# NMEA_BatteryMonitor_ESP32_D1_Mini.net
KiCad netlist of a schematic drawn in EAGLE
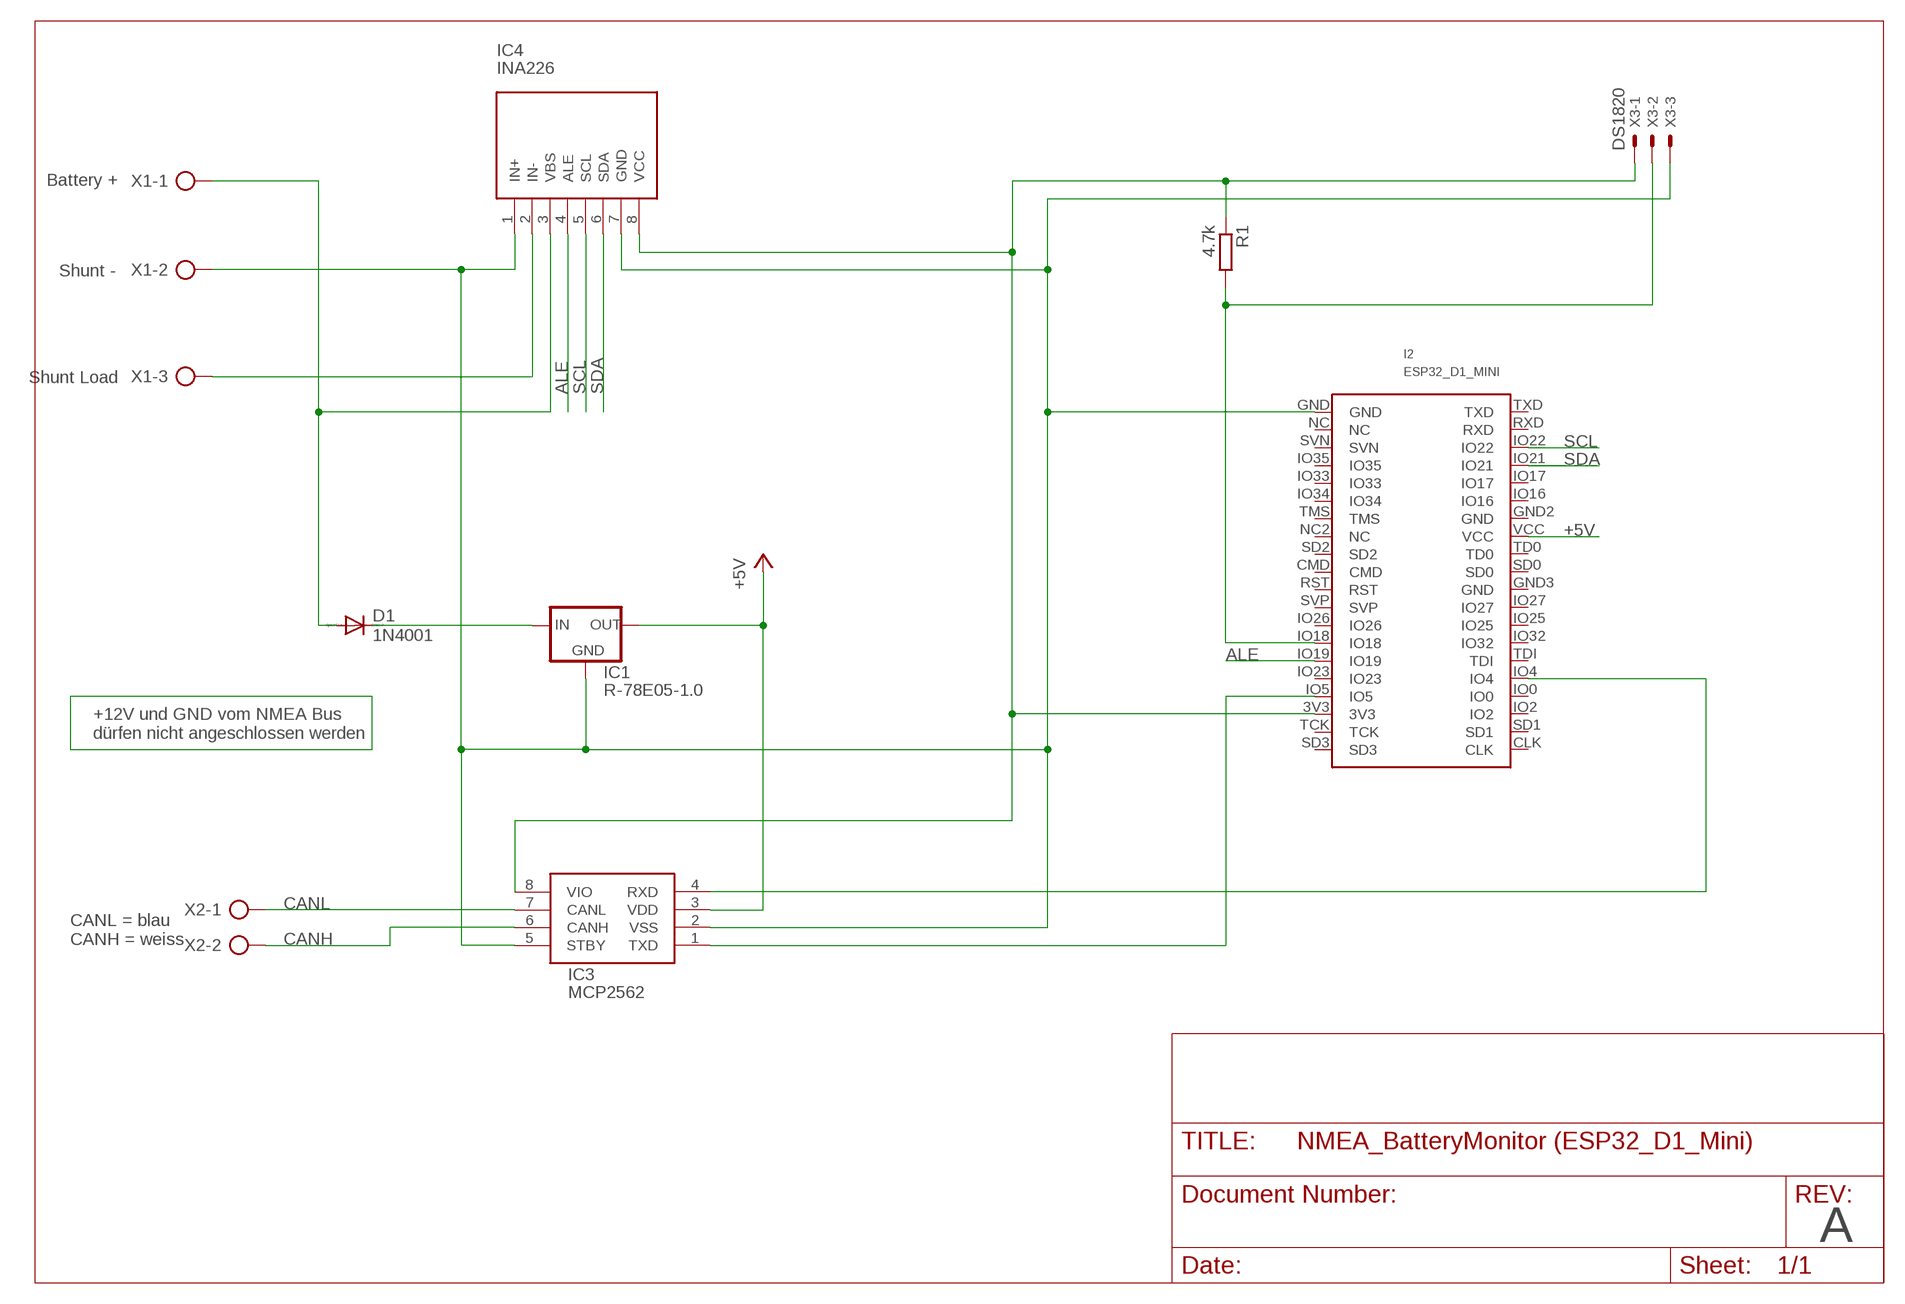
[diagram p0: schematic, sheet 1]

(export (version "E")
  (design (tool "Eeschema 10.0.6"))
  (components
    (comp (ref "D1")
      (value "1N4001")
      (footprint "eagle-import:SOD80")
      (libsource (lib "eagle-import") (part "1N4148"))
    )
    (comp (ref "I2")
      (value "ESP32_D1_MINI")
      (footprint "eagle-import:ESP32_D1_MINI")
      (libsource (lib "eagle-import") (part "ESP32_D1_MINI"))
    )
    (comp (ref "IC1")
      (value "R-78E05-1.0")
      (footprint "eagle-import:R-78E-XX1.0")
      (libsource (lib "eagle-import") (part "R-78E-XX1.0"))
    )
    (comp (ref "IC3")
      (value "MCP2562")
      (footprint "eagle-import:SO-8")
      (libsource (lib "eagle-import") (part "MCP2562SMD"))
    )
    (comp (ref "IC4")
      (value "INA226")
      (footprint "eagle-import:INA226")
      (libsource (lib "eagle-import") (part "INA226"))
    )
    (comp (ref "R1")
      (value "4.7k")
      (footprint "eagle-import:R0805")
      (libsource (lib "eagle-import") (part "R-EU_R0805"))
    )
    (comp (ref "X1")
      (value "AK500/3")
      (footprint "eagle-import:AK500_3")
      (libsource (lib "eagle-import") (part "AK500/3"))
    )
    (comp (ref "X2")
      (value "AK500/2")
      (footprint "eagle-import:AK500_2")
      (libsource (lib "eagle-import") (part "AK500/2"))
    )
    (comp (ref "X3")
      (value "DS1820")
      (footprint "eagle-import:22-23-2031")
      (fields (field (name "MF") "MOLEX") (field (name "MPN") "22-23-2031"))
      (libsource (lib "eagle-import") (part "22-23-2031"))
    )
  )
  (nets
    (net (code "1") (name "+5V") (class "Default")
      (node (ref "I2") (pin "VCC") (pinfunction "VCC_VCC") (pintype "bidirectional"))
      (node (ref "IC1") (pin "OUT") (pinfunction "OUT_OUT") (pintype "passive"))
      (node (ref "IC3") (pin "3") (pinfunction "VDD_3") (pintype "bidirectional"))
    )
    (net (code "2") (name "/ALE") (class "Default")
      (node (ref "I2") (pin "IO19") (pinfunction "IO19_IO19") (pintype "bidirectional"))
      (node (ref "IC4") (pin "4") (pinfunction "ALE_4") (pintype "bidirectional"))
    )
    (net (code "3") (name "/CANH") (class "Default")
      (node (ref "IC3") (pin "6") (pinfunction "CANH_6") (pintype "bidirectional"))
      (node (ref "X2") (pin "2") (pinfunction "KL_2") (pintype "passive"))
    )
    (net (code "4") (name "/CANL") (class "Default")
      (node (ref "IC3") (pin "7") (pinfunction "CANL_7") (pintype "bidirectional"))
      (node (ref "X2") (pin "1") (pinfunction "KL_1") (pintype "passive"))
    )
    (net (code "5") (name "/SCL") (class "Default")
      (node (ref "I2") (pin "IO22") (pinfunction "IO22_IO22") (pintype "bidirectional"))
      (node (ref "IC4") (pin "5") (pinfunction "SCL_5") (pintype "bidirectional"))
    )
    (net (code "6") (name "/SDA") (class "Default")
      (node (ref "I2") (pin "IO21") (pinfunction "IO21_IO21") (pintype "bidirectional"))
      (node (ref "IC4") (pin "6") (pinfunction "SDA_6") (pintype "bidirectional"))
    )
    (net (code "7") (name "Net-(D1-PadC)") (class "Default")
      (node (ref "D1") (pin "C") (pinfunction "C_C") (pintype "passive"))
      (node (ref "IC1") (pin "IN") (pinfunction "IN_IN") (pintype "input"))
    )
    (net (code "8") (name "Net-(IC3-RXD)") (class "Default")
      (node (ref "I2") (pin "IO4") (pinfunction "IO4_IO4") (pintype "bidirectional"))
      (node (ref "IC3") (pin "4") (pinfunction "RXD_4") (pintype "bidirectional"))
    )
    (net (code "9") (name "Net-(IC3-STBY)") (class "Default")
      (node (ref "I2") (pin "GND") (pinfunction "GND_GND") (pintype "bidirectional"))
      (node (ref "IC1") (pin "GND") (pinfunction "GND_GND") (pintype "input"))
      (node (ref "IC3") (pin "2") (pinfunction "VSS_2") (pintype "bidirectional"))
      (node (ref "IC3") (pin "5") (pinfunction "STBY_5") (pintype "bidirectional"))
      (node (ref "IC4") (pin "1") (pinfunction "IN+_1") (pintype "bidirectional"))
      (node (ref "IC4") (pin "7") (pinfunction "GND_7") (pintype "power_in"))
      (node (ref "X1") (pin "2") (pinfunction "KL_2") (pintype "passive"))
      (node (ref "X3") (pin "3") (pinfunction "S_3") (pintype "passive"))
    )
    (net (code "10") (name "Net-(IC3-TXD)") (class "Default")
      (node (ref "I2") (pin "IO5") (pinfunction "IO5_IO5") (pintype "bidirectional"))
      (node (ref "IC3") (pin "1") (pinfunction "TXD_1") (pintype "bidirectional"))
    )
    (net (code "11") (name "Net-(IC3-VIO)") (class "Default")
      (node (ref "I2") (pin "3V3") (pinfunction "3V3_3V3") (pintype "bidirectional"))
      (node (ref "IC3") (pin "8") (pinfunction "VIO_8") (pintype "bidirectional"))
      (node (ref "IC4") (pin "8") (pinfunction "VCC_8") (pintype "power_in"))
      (node (ref "R1") (pin "1") (pinfunction "1_1") (pintype "passive"))
      (node (ref "X3") (pin "1") (pinfunction "S_1") (pintype "passive"))
    )
    (net (code "12") (name "Net-(IC4-IN-)") (class "Default")
      (node (ref "IC4") (pin "2") (pinfunction "IN-_2") (pintype "bidirectional"))
      (node (ref "X1") (pin "3") (pinfunction "KL_3") (pintype "passive"))
    )
    (net (code "13") (name "Net-(IC4-VBS)") (class "Default")
      (node (ref "D1") (pin "A") (pinfunction "A_A") (pintype "passive"))
      (node (ref "IC4") (pin "3") (pinfunction "VBS_3") (pintype "bidirectional"))
      (node (ref "X1") (pin "1") (pinfunction "KL_1") (pintype "passive"))
    )
    (net (code "14") (name "Net-(X3B-S)") (class "Default")
      (node (ref "I2") (pin "IO18") (pinfunction "IO18_IO18") (pintype "bidirectional"))
      (node (ref "R1") (pin "2") (pinfunction "2_2") (pintype "passive"))
      (node (ref "X3") (pin "2") (pinfunction "S_2") (pintype "passive"))
    )
    (net (code "15") (name "unconnected-(I2-GND-PadGND2)") (class "Default")
      (node (ref "I2") (pin "GND2") (pinfunction "GND_GND2") (pintype "bidirectional"))
    )
    (net (code "16") (name "unconnected-(I2-GND-PadGND3)") (class "Default")
      (node (ref "I2") (pin "GND3") (pinfunction "GND_GND3") (pintype "bidirectional"))
    )
    (net (code "17") (name "unconnected-(I2-NC-PadNC2)") (class "Default")
      (node (ref "I2") (pin "NC2") (pinfunction "NC_NC2") (pintype "bidirectional"))
    )
    (net (code "18") (name "unconnected-(I2-PadCLK)") (class "Default")
      (node (ref "I2") (pin "CLK") (pinfunction "CLK_CLK") (pintype "bidirectional"))
    )
    (net (code "19") (name "unconnected-(I2-PadCMD)") (class "Default")
      (node (ref "I2") (pin "CMD") (pinfunction "CMD_CMD") (pintype "bidirectional"))
    )
    (net (code "20") (name "unconnected-(I2-PadIO0)") (class "Default")
      (node (ref "I2") (pin "IO0") (pinfunction "IO0_IO0") (pintype "bidirectional"))
    )
    (net (code "21") (name "unconnected-(I2-PadIO2)") (class "Default")
      (node (ref "I2") (pin "IO2") (pinfunction "IO2_IO2") (pintype "bidirectional"))
    )
    (net (code "22") (name "unconnected-(I2-PadIO16)") (class "Default")
      (node (ref "I2") (pin "IO16") (pinfunction "IO16_IO16") (pintype "bidirectional"))
    )
    (net (code "23") (name "unconnected-(I2-PadIO17)") (class "Default")
      (node (ref "I2") (pin "IO17") (pinfunction "IO17_IO17") (pintype "bidirectional"))
    )
    (net (code "24") (name "unconnected-(I2-PadIO23)") (class "Default")
      (node (ref "I2") (pin "IO23") (pinfunction "IO23_IO23") (pintype "bidirectional"))
    )
    (net (code "25") (name "unconnected-(I2-PadIO25)") (class "Default")
      (node (ref "I2") (pin "IO25") (pinfunction "IO25_IO25") (pintype "bidirectional"))
    )
    (net (code "26") (name "unconnected-(I2-PadIO26)") (class "Default")
      (node (ref "I2") (pin "IO26") (pinfunction "IO26_IO26") (pintype "bidirectional"))
    )
    (net (code "27") (name "unconnected-(I2-PadIO27)") (class "Default")
      (node (ref "I2") (pin "IO27") (pinfunction "IO27_IO27") (pintype "bidirectional"))
    )
    (net (code "28") (name "unconnected-(I2-PadIO32)") (class "Default")
      (node (ref "I2") (pin "IO32") (pinfunction "IO32_IO32") (pintype "bidirectional"))
    )
    (net (code "29") (name "unconnected-(I2-PadIO33)") (class "Default")
      (node (ref "I2") (pin "IO33") (pinfunction "IO33_IO33") (pintype "bidirectional"))
    )
    (net (code "30") (name "unconnected-(I2-PadIO34)") (class "Default")
      (node (ref "I2") (pin "IO34") (pinfunction "IO34_IO34") (pintype "bidirectional"))
    )
    (net (code "31") (name "unconnected-(I2-PadIO35)") (class "Default")
      (node (ref "I2") (pin "IO35") (pinfunction "IO35_IO35") (pintype "bidirectional"))
    )
    (net (code "32") (name "unconnected-(I2-PadNC)") (class "Default")
      (node (ref "I2") (pin "NC") (pinfunction "NC_NC") (pintype "bidirectional"))
    )
    (net (code "33") (name "unconnected-(I2-PadRST)") (class "Default")
      (node (ref "I2") (pin "RST") (pinfunction "RST_RST") (pintype "bidirectional"))
    )
    (net (code "34") (name "unconnected-(I2-PadRXD)") (class "Default")
      (node (ref "I2") (pin "RXD") (pinfunction "RXD_RXD") (pintype "bidirectional"))
    )
    (net (code "35") (name "unconnected-(I2-PadSD0)") (class "Default")
      (node (ref "I2") (pin "SD0") (pinfunction "SD0_SD0") (pintype "bidirectional"))
    )
    (net (code "36") (name "unconnected-(I2-PadSD1)") (class "Default")
      (node (ref "I2") (pin "SD1") (pinfunction "SD1_SD1") (pintype "bidirectional"))
    )
    (net (code "37") (name "unconnected-(I2-PadSD2)") (class "Default")
      (node (ref "I2") (pin "SD2") (pinfunction "SD2_SD2") (pintype "bidirectional"))
    )
    (net (code "38") (name "unconnected-(I2-PadSD3)") (class "Default")
      (node (ref "I2") (pin "SD3") (pinfunction "SD3_SD3") (pintype "bidirectional"))
    )
    (net (code "39") (name "unconnected-(I2-PadSVN)") (class "Default")
      (node (ref "I2") (pin "SVN") (pinfunction "SVN_SVN") (pintype "bidirectional"))
    )
    (net (code "40") (name "unconnected-(I2-PadSVP)") (class "Default")
      (node (ref "I2") (pin "SVP") (pinfunction "SVP_SVP") (pintype "bidirectional"))
    )
    (net (code "41") (name "unconnected-(I2-PadTCK)") (class "Default")
      (node (ref "I2") (pin "TCK") (pinfunction "TCK_TCK") (pintype "bidirectional"))
    )
    (net (code "42") (name "unconnected-(I2-PadTD0)") (class "Default")
      (node (ref "I2") (pin "TD0") (pinfunction "TD0_TD0") (pintype "bidirectional"))
    )
    (net (code "43") (name "unconnected-(I2-PadTDI)") (class "Default")
      (node (ref "I2") (pin "TDI") (pinfunction "TDI_TDI") (pintype "bidirectional"))
    )
    (net (code "44") (name "unconnected-(I2-PadTMS)") (class "Default")
      (node (ref "I2") (pin "TMS") (pinfunction "TMS_TMS") (pintype "bidirectional"))
    )
    (net (code "45") (name "unconnected-(I2-PadTXD)") (class "Default")
      (node (ref "I2") (pin "TXD") (pinfunction "TXD_TXD") (pintype "bidirectional"))
    )
  )
)
